# UKU207xx_power_board.net
KiCad netlist of a schematic drawn in Altium Designer
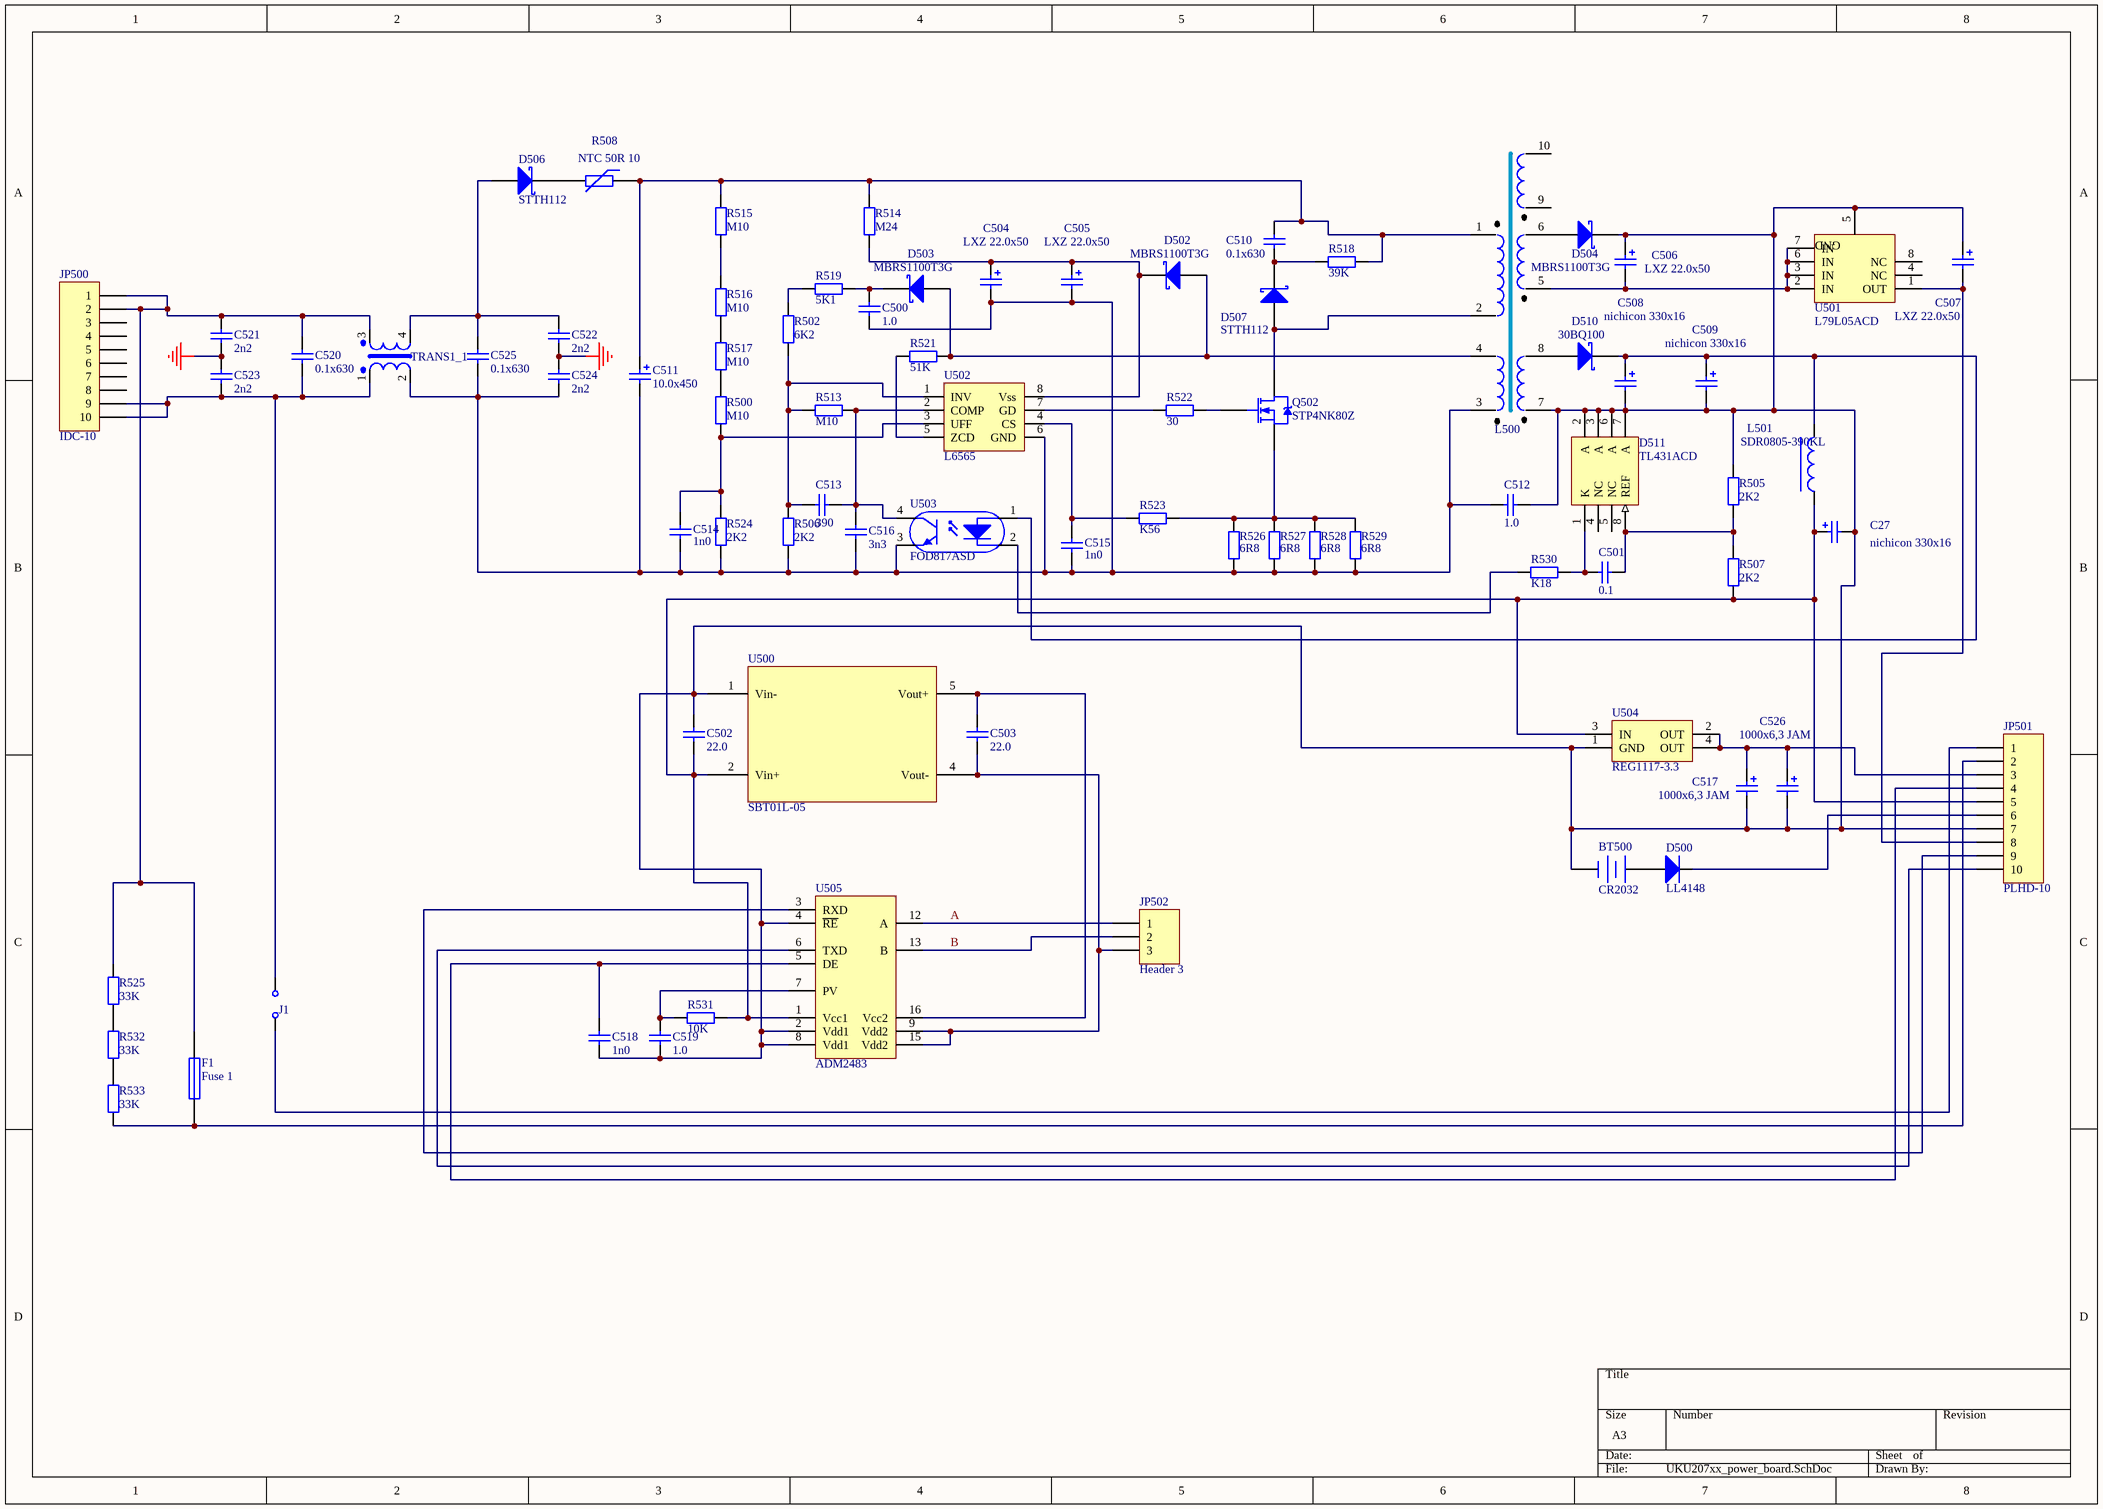
[diagram p0: UKU207xx_power_board.SchDoc]

(export (version "E")
  (design (tool "Eeschema 10.0.6"))
  (components
    (comp (ref "BT500")
      (value "CR2032")
      (footprint "BAT_SUPP")
      (description "Multicell Battery")
      (fields (field (name "MANUFACTURER") "Generic Components") (field (name "PUBLISHER") "Altium Limited"))
      (libsource (lib "Miscellaneous Devices") (part "Battery"))
    )
    (comp (ref "C27")
      (value "nichicon 330x16")
      (footprint "el3")
      (description "Polarized Capacitor (Radial)")
      (fields (field (name "MANUFACTURER") "Generic Components") (field (name "PUBLISHER") "Altium Limited"))
      (libsource (lib "PAL") (part "Cap Pol1"))
    )
    (comp (ref "C500")
      (value "1.0")
      (footprint "_1206")
      (description "Capacitor (Semiconductor SIM Model)")
      (fields (field (name "MANUFACTURER") "Generic Components") (field (name "PUBLISHER") "Altium Limited"))
      (libsource (lib "Miscellaneous Devices") (part "Cap Semi"))
    )
    (comp (ref "C501")
      (value "0.1")
      (footprint "_1206")
      (description "Capacitor (Semiconductor SIM Model)")
      (fields (field (name "MANUFACTURER") "Generic Components") (field (name "PUBLISHER") "Altium Limited"))
      (libsource (lib "Miscellaneous Devices") (part "Cap Semi"))
    )
    (comp (ref "C502")
      (value "22.0")
      (footprint "_1206")
      (description "Capacitor (Semiconductor SIM Model)")
      (fields (field (name "MANUFACTURER") "Generic Components") (field (name "PUBLISHER") "Altium Limited"))
      (libsource (lib "Miscellaneous Devices") (part "Cap Semi"))
    )
    (comp (ref "C503")
      (value "22.0")
      (footprint "_1206")
      (description "Capacitor (Semiconductor SIM Model)")
      (fields (field (name "MANUFACTURER") "Generic Components") (field (name "PUBLISHER") "Altium Limited"))
      (libsource (lib "Miscellaneous Devices") (part "Cap Semi"))
    )
    (comp (ref "C504")
      (value "LXZ 22.0x50")
      (footprint "el3")
      (description "Polarized Capacitor (Radial)")
      (fields (field (name "MANUFACTURER") "Generic Components") (field (name "PUBLISHER") "Altium Limited"))
      (libsource (lib "PAL") (part "Cap Pol1"))
    )
    (comp (ref "C505")
      (value "LXZ 22.0x50")
      (footprint "el3")
      (description "Polarized Capacitor (Radial)")
      (fields (field (name "MANUFACTURER") "Generic Components") (field (name "PUBLISHER") "Altium Limited"))
      (libsource (lib "PAL") (part "Cap Pol1"))
    )
    (comp (ref "C506")
      (value "LXZ 22.0x50")
      (footprint "el3")
      (description "Polarized Capacitor (Radial)")
      (fields (field (name "MANUFACTURER") "Generic Components") (field (name "PUBLISHER") "Altium Limited"))
      (libsource (lib "PAL") (part "Cap Pol1"))
    )
    (comp (ref "C507")
      (value "LXZ 22.0x50")
      (footprint "el3")
      (description "Polarized Capacitor (Radial)")
      (fields (field (name "MANUFACTURER") "Generic Components") (field (name "PUBLISHER") "Altium Limited"))
      (libsource (lib "PAL") (part "Cap Pol1"))
    )
    (comp (ref "C508")
      (value "nichicon 330x16")
      (footprint "el3")
      (description "Polarized Capacitor (Radial)")
      (fields (field (name "MANUFACTURER") "Generic Components") (field (name "PUBLISHER") "Altium Limited"))
      (libsource (lib "PAL") (part "Cap Pol1"))
    )
    (comp (ref "C509")
      (value "nichicon 330x16")
      (footprint "el3")
      (description "Polarized Capacitor (Radial)")
      (fields (field (name "MANUFACTURER") "Generic Components") (field (name "PUBLISHER") "Altium Limited"))
      (libsource (lib "PAL") (part "Cap Pol1"))
    )
    (comp (ref "C510")
      (value "0.1x630")
      (footprint "c15")
      (description "Capacitor (Semiconductor SIM Model)")
      (fields (field (name "MANUFACTURER") "Generic Components") (field (name "PUBLISHER") "Altium Limited"))
      (libsource (lib "Miscellaneous Devices") (part "Cap Semi"))
    )
    (comp (ref "C511")
      (value "10.0x450")
      (footprint "el_15_25_h")
      (description "Polarized Capacitor (Radial)")
      (fields (field (name "MANUFACTURER") "Generic Components") (field (name "PUBLISHER") "Altium Limited"))
      (libsource (lib "PAL") (part "Cap Pol1"))
    )
    (comp (ref "C512")
      (value "1.0")
      (footprint "C8")
      (description "Capacitor (Semiconductor SIM Model)")
      (fields (field (name "MANUFACTURER") "Generic Components") (field (name "PUBLISHER") "Altium Limited"))
      (libsource (lib "Miscellaneous Devices") (part "Cap Semi"))
    )
    (comp (ref "C513")
      (value "390")
      (footprint "_1206")
      (description "Capacitor (Semiconductor SIM Model)")
      (fields (field (name "MANUFACTURER") "Generic Components") (field (name "PUBLISHER") "Altium Limited"))
      (libsource (lib "Miscellaneous Devices") (part "Cap Semi"))
    )
    (comp (ref "C514")
      (value "1n0")
      (footprint "_1206")
      (description "Capacitor (Semiconductor SIM Model)")
      (fields (field (name "MANUFACTURER") "Generic Components") (field (name "PUBLISHER") "Altium Limited"))
      (libsource (lib "Miscellaneous Devices") (part "Cap Semi"))
    )
    (comp (ref "C515")
      (value "1n0")
      (footprint "_1206")
      (description "Capacitor (Semiconductor SIM Model)")
      (fields (field (name "MANUFACTURER") "Generic Components") (field (name "PUBLISHER") "Altium Limited"))
      (libsource (lib "Miscellaneous Devices") (part "Cap Semi"))
    )
    (comp (ref "C516")
      (value "3n3")
      (footprint "_1206")
      (description "Capacitor (Semiconductor SIM Model)")
      (fields (field (name "MANUFACTURER") "Generic Components") (field (name "PUBLISHER") "Altium Limited"))
      (libsource (lib "Miscellaneous Devices") (part "Cap Semi"))
    )
    (comp (ref "C517")
      (value "1000x6,3 JAM")
      (footprint "el3")
      (description "Polarized Capacitor (Radial)")
      (fields (field (name "MANUFACTURER") "Generic Components") (field (name "PUBLISHER") "Altium Limited"))
      (libsource (lib "PAL") (part "Cap Pol1"))
    )
    (comp (ref "C518")
      (value "1n0")
      (footprint "_1206")
      (description "Capacitor (Semiconductor SIM Model)")
      (fields (field (name "MANUFACTURER") "Generic Components") (field (name "PUBLISHER") "Altium Limited"))
      (libsource (lib "Miscellaneous Devices") (part "Cap Semi"))
    )
    (comp (ref "C519")
      (value "1.0")
      (footprint "_1206")
      (description "Capacitor (Semiconductor SIM Model)")
      (fields (field (name "MANUFACTURER") "Generic Components") (field (name "PUBLISHER") "Altium Limited"))
      (libsource (lib "Miscellaneous Devices") (part "Cap Semi"))
    )
    (comp (ref "C520")
      (value "0.1x630")
      (footprint "c15")
      (description "Capacitor (Semiconductor SIM Model)")
      (fields (field (name "MANUFACTURER") "Generic Components") (field (name "PUBLISHER") "Altium Limited"))
      (libsource (lib "Miscellaneous Devices") (part "Cap Semi"))
    )
    (comp (ref "C521")
      (value "2n2")
      (footprint "C8")
      (description "Capacitor (Semiconductor SIM Model)")
      (fields (field (name "MANUFACTURER") "Generic Components") (field (name "PUBLISHER") "Altium Limited"))
      (libsource (lib "Miscellaneous Devices") (part "Cap Semi"))
    )
    (comp (ref "C522")
      (value "2n2")
      (footprint "c8")
      (description "Capacitor (Semiconductor SIM Model)")
      (fields (field (name "MANUFACTURER") "Generic Components") (field (name "PUBLISHER") "Altium Limited"))
      (libsource (lib "Miscellaneous Devices") (part "Cap Semi"))
    )
    (comp (ref "C523")
      (value "2n2")
      (footprint "c8")
      (description "Capacitor (Semiconductor SIM Model)")
      (fields (field (name "MANUFACTURER") "Generic Components") (field (name "PUBLISHER") "Altium Limited"))
      (libsource (lib "Miscellaneous Devices") (part "Cap Semi"))
    )
    (comp (ref "C524")
      (value "2n2")
      (footprint "c8")
      (description "Capacitor (Semiconductor SIM Model)")
      (fields (field (name "MANUFACTURER") "Generic Components") (field (name "PUBLISHER") "Altium Limited"))
      (libsource (lib "Miscellaneous Devices") (part "Cap Semi"))
    )
    (comp (ref "C525")
      (value "0.1х630")
      (footprint "c15")
      (description "Capacitor (Semiconductor SIM Model)")
      (fields (field (name "MANUFACTURER") "Generic Components") (field (name "PUBLISHER") "Altium Limited"))
      (libsource (lib "Miscellaneous Devices") (part "Cap Semi"))
    )
    (comp (ref "C526")
      (value "1000x6,3 JAM")
      (footprint "el3")
      (description "Polarized Capacitor (Radial)")
      (fields (field (name "MANUFACTURER") "Generic Components") (field (name "PUBLISHER") "Altium Limited"))
      (libsource (lib "PAL") (part "Cap Pol1"))
    )
    (comp (ref "D500")
      (value "LL4148")
      (footprint "_1206d")
      (description "Default Diode")
      (fields (field (name "MANUFACTURER") "Generic Components") (field (name "PUBLISHER") "Altium Limited"))
      (libsource (lib "PAL") (part "Diode"))
    )
    (comp (ref "D502")
      (value "MBRS1100T3G")
      (footprint "D_6_3")
      (description "Schottky Rectifier")
      (fields
        (field (name "MANUFACTURER") "International Rectifier")
        (field (name "PUBLISHER") "Altium Limited")
      )
      (libsource (lib "IR Discrete Diode") (part "10BQ015"))
    )
    (comp (ref "D503")
      (value "MBRS1100T3G")
      (footprint "D_6_3")
      (description "Schottky Rectifier")
      (fields
        (field (name "MANUFACTURER") "International Rectifier")
        (field (name "PUBLISHER") "Altium Limited")
      )
      (libsource (lib "IR Discrete Diode") (part "10BQ015"))
    )
    (comp (ref "D504")
      (value "MBRS1100T3G")
      (footprint "D_6_3")
      (description "Schottky Rectifier")
      (fields
        (field (name "MANUFACTURER") "International Rectifier")
        (field (name "PUBLISHER") "Altium Limited")
      )
      (libsource (lib "IR Discrete Diode") (part "10BQ015"))
    )
    (comp (ref "D506")
      (value "STTH112")
      (footprint "D_6_3")
      (description "Schottky Diode")
      (fields
        (field (name "MANUFACTURER") "International Rectifier")
        (field (name "PUBLISHER") "Altium Limited")
      )
      (libsource (lib "IR Discrete Diode") (part "10BQ015"))
    )
    (comp (ref "D507")
      (value "STTH112")
      (footprint "D_6_3")
      (description "Schottky Diode")
      (fields
        (field (name "MANUFACTURER") "International Rectifier")
        (field (name "PUBLISHER") "Altium Limited")
      )
      (libsource (lib "IR Discrete Diode") (part "10BQ015"))
    )
    (comp (ref "D510")
      (value "30BQ100")
      (footprint "30BQ100")
      (description "Schottky Rectifier")
      (fields
        (field (name "MANUFACTURER") "International Rectifier")
        (field (name "PUBLISHER") "Altium Limited")
      )
      (libsource (lib "IR Discrete Diode") (part "10BQ015"))
    )
    (comp (ref "D511")
      (value "TL431ACD")
      (footprint "SO-G8")
      (description "Programmable Precision Reference")
      (fields (field (name "MANUFACTURER") "Motorola") (field (name "PUBLISHER") "Altium Limited"))
      (libsource (lib "Motorola Power Management Voltage Reference") (part "TL431ACD"))
    )
    (comp (ref "F1")
      (value "Fuse 1")
      (footprint "PIN-W2/E2.8")
      (description "Fuse")
      (fields (field (name "MANUFACTURER") "Generic Components") (field (name "PUBLISHER") "Altium Limited"))
      (libsource (lib "Miscellaneous Devices") (part "Fuse 1"))
    )
    (comp (ref "J1")
      (value "~")
      (footprint "BT5-2")
      (description "Switch")
      (fields (field (name "MANUFACTURER") "Generic Components") (field (name "PUBLISHER") "Altium Limited"))
      (libsource (lib "PAL") (part "JMP"))
    )
    (comp (ref "JP500")
      (value "IDC-10")
      (footprint "HDR2X5")
      (description "Header, 10-Pin")
      (fields (field (name "MANUFACTURER") "Generic Components") (field (name "PUBLISHER") "Altium Limited"))
      (libsource (lib "") (part "Header 10_1"))
    )
    (comp (ref "JP501")
      (value "PLHD-10")
      (footprint "HDR2X5")
      (description "Header, 10-Pin")
      (fields (field (name "MANUFACTURER") "Generic Components") (field (name "PUBLISHER") "Altium Limited"))
      (libsource (lib "Miscellaneous Connectors") (part "Header 10"))
    )
    (comp (ref "JP502")
      (value "Header 3")
      (footprint "2EDG-5.08-3P")
      (description "Header, 3-Pin")
      (fields (field (name "MANUFACTURER") "Generic Components") (field (name "PUBLISHER") "Altium Limited"))
      (libsource (lib "Miscellaneous Connectors") (part "Header 3"))
    )
    (comp (ref "L500")
      (value "L220-K10")
      (footprint "trans_ring1")
      (description "Дроссель")
      (libsource (lib "PAL") (part "L1_dc_2"))
    )
    (comp (ref "L501")
      (value "SDR0805-390KL")
      (footprint "L10x10")
      (description "Magnetic-Core Inductor")
      (fields (field (name "MANUFACTURER") "Generic Components") (field (name "PUBLISHER") "Altium Limited"))
      (libsource (lib "PAL") (part "Inductor Konstr 2"))
    )
    (comp (ref "Q502")
      (value "STP4NK80Z")
      (footprint "TO220_h")
      (description "N-Channel Power MOSFET")
      (fields (field (name "MANUFACTURER") "Generic Components") (field (name "PUBLISHER") "Altium Limited"))
      (libsource (lib "Miscellaneous Devices") (part "NMOS-2"))
    )
    (comp (ref "R500")
      (value "M10")
      (footprint "_1206")
      (description "Resistor")
      (fields (field (name "MANUFACTURER") "Generic Components") (field (name "PUBLISHER") "Altium Limited"))
      (libsource (lib "Miscellaneous Devices") (part "Res2"))
    )
    (comp (ref "R502")
      (value "6K2")
      (footprint "_1206")
      (description "Resistor")
      (fields (field (name "MANUFACTURER") "Generic Components") (field (name "PUBLISHER") "Altium Limited"))
      (libsource (lib "Miscellaneous Devices") (part "Res2"))
    )
    (comp (ref "R505")
      (value "2K2")
      (footprint "_1206")
      (description "Resistor")
      (fields (field (name "MANUFACTURER") "Generic Components") (field (name "PUBLISHER") "Altium Limited"))
      (libsource (lib "Miscellaneous Devices") (part "Res2"))
    )
    (comp (ref "R506")
      (value "2K2")
      (footprint "_1206")
      (description "Resistor")
      (fields (field (name "MANUFACTURER") "Generic Components") (field (name "PUBLISHER") "Altium Limited"))
      (libsource (lib "Miscellaneous Devices") (part "Res2"))
    )
    (comp (ref "R507")
      (value "2K2")
      (footprint "_1206")
      (description "Resistor")
      (fields (field (name "MANUFACTURER") "Generic Components") (field (name "PUBLISHER") "Altium Limited"))
      (libsource (lib "Miscellaneous Devices") (part "Res2"))
    )
    (comp (ref "R508")
      (value "NTC 50R 10")
      (footprint "JVR07N")
      (description "Varistor (Voltage-Sensitive Resistor)")
      (fields (field (name "MANUFACTURER") "Generic Components") (field (name "PUBLISHER") "Altium Limited"))
      (libsource (lib "Miscellaneous Devices") (part "Res Varistor"))
    )
    (comp (ref "R513")
      (value "M10")
      (footprint "_1206")
      (description "Resistor")
      (fields (field (name "MANUFACTURER") "Generic Components") (field (name "PUBLISHER") "Altium Limited"))
      (libsource (lib "") (part "Res2_1"))
    )
    (comp (ref "R514")
      (value "M24")
      (footprint "AXIAL-0.7")
      (description "Resistor")
      (fields (field (name "MANUFACTURER") "Generic Components") (field (name "PUBLISHER") "Altium Limited"))
      (libsource (lib "Miscellaneous Devices") (part "Res2"))
    )
    (comp (ref "R515")
      (value "M10")
      (footprint "_1206")
      (description "Resistor")
      (fields (field (name "MANUFACTURER") "Generic Components") (field (name "PUBLISHER") "Altium Limited"))
      (libsource (lib "Miscellaneous Devices") (part "Res2"))
    )
    (comp (ref "R516")
      (value "M10")
      (footprint "_1206")
      (description "Resistor")
      (fields (field (name "MANUFACTURER") "Generic Components") (field (name "PUBLISHER") "Altium Limited"))
      (libsource (lib "Miscellaneous Devices") (part "Res2"))
    )
    (comp (ref "R517")
      (value "M10")
      (footprint "_1206")
      (description "Resistor")
      (fields (field (name "MANUFACTURER") "Generic Components") (field (name "PUBLISHER") "Altium Limited"))
      (libsource (lib "Miscellaneous Devices") (part "Res2"))
    )
    (comp (ref "R518")
      (value "39K")
      (footprint "AXIAL-0.7")
      (description "Resistor")
      (fields (field (name "MANUFACTURER") "Generic Components") (field (name "PUBLISHER") "Altium Limited"))
      (libsource (lib "") (part "Res2_1"))
    )
    (comp (ref "R519")
      (value "5K1")
      (footprint "_1206")
      (description "Resistor")
      (fields (field (name "MANUFACTURER") "Generic Components") (field (name "PUBLISHER") "Altium Limited"))
      (libsource (lib "") (part "Res2_1"))
    )
    (comp (ref "R521")
      (value "51K")
      (footprint "_1206")
      (description "Resistor")
      (fields (field (name "MANUFACTURER") "Generic Components") (field (name "PUBLISHER") "Altium Limited"))
      (libsource (lib "") (part "Res2_1"))
    )
    (comp (ref "R522")
      (value "30")
      (footprint "_1206")
      (description "Resistor")
      (fields (field (name "MANUFACTURER") "Generic Components") (field (name "PUBLISHER") "Altium Limited"))
      (libsource (lib "") (part "Res2_1"))
    )
    (comp (ref "R523")
      (value "K56")
      (footprint "_1206")
      (description "Resistor")
      (fields (field (name "MANUFACTURER") "Generic Components") (field (name "PUBLISHER") "Altium Limited"))
      (libsource (lib "") (part "Res2_1"))
    )
    (comp (ref "R524")
      (value "2K2")
      (footprint "_1206")
      (description "Resistor")
      (fields (field (name "MANUFACTURER") "Generic Components") (field (name "PUBLISHER") "Altium Limited"))
      (libsource (lib "Miscellaneous Devices") (part "Res2"))
    )
    (comp (ref "R525")
      (value "33K")
      (footprint "_1206")
      (description "Resistor")
      (fields (field (name "MANUFACTURER") "Generic Components") (field (name "PUBLISHER") "Altium Limited"))
      (libsource (lib "Miscellaneous Devices") (part "Res2"))
    )
    (comp (ref "R526")
      (value "6R8")
      (footprint "_1206")
      (description "Resistor")
      (fields (field (name "MANUFACTURER") "Generic Components") (field (name "PUBLISHER") "Altium Limited"))
      (libsource (lib "") (part "Res2_2"))
    )
    (comp (ref "R527")
      (value "6R8")
      (footprint "_1206")
      (description "Resistor")
      (fields (field (name "MANUFACTURER") "Generic Components") (field (name "PUBLISHER") "Altium Limited"))
      (libsource (lib "") (part "Res2_2"))
    )
    (comp (ref "R528")
      (value "6R8")
      (footprint "_1206")
      (description "Resistor")
      (fields (field (name "MANUFACTURER") "Generic Components") (field (name "PUBLISHER") "Altium Limited"))
      (libsource (lib "") (part "Res2_2"))
    )
    (comp (ref "R529")
      (value "6R8")
      (footprint "_1206")
      (description "Resistor")
      (fields (field (name "MANUFACTURER") "Generic Components") (field (name "PUBLISHER") "Altium Limited"))
      (libsource (lib "") (part "Res2_2"))
    )
    (comp (ref "R530")
      (value "K18")
      (footprint "_1206")
      (description "Resistor")
      (fields (field (name "MANUFACTURER") "Generic Components") (field (name "PUBLISHER") "Altium Limited"))
      (libsource (lib "") (part "Res2_1"))
    )
    (comp (ref "R531")
      (value "10K")
      (footprint "_1206")
      (description "Resistor")
      (fields (field (name "MANUFACTURER") "Generic Components") (field (name "PUBLISHER") "Altium Limited"))
      (libsource (lib "") (part "Res2_1"))
    )
    (comp (ref "R532")
      (value "33K")
      (footprint "_1206")
      (description "Resistor")
      (fields (field (name "MANUFACTURER") "Generic Components") (field (name "PUBLISHER") "Altium Limited"))
      (libsource (lib "Miscellaneous Devices") (part "Res2"))
    )
    (comp (ref "R533")
      (value "33K")
      (footprint "_1206")
      (description "Resistor")
      (fields (field (name "MANUFACTURER") "Generic Components") (field (name "PUBLISHER") "Altium Limited"))
      (libsource (lib "Miscellaneous Devices") (part "Res2"))
    )
    (comp (ref "T500")
      (value "TRANS1_1")
      (footprint "3030R4")
      (fields (field (name "MANUFACTURER") "Generic Components") (field (name "PUBLISHER") "Altium Limited"))
      (libsource (lib "PAL") (part "TRANS1_1"))
    )
    (comp (ref "U500") (value "SBT01L-05") (footprint "SBT01DET01") (libsource (lib "PAL") (part "SBT01L")))
    (comp (ref "U501")
      (value "L79L05ACD")
      (footprint "SO-G8")
      (description "Negative Voltage Regulator")
      (fields (field (name "MANUFACTURER") "ST-Microelectronics") (field (name "PUBLISHER") "Altium Limited"))
      (libsource (lib "ST Power Mgt Voltage Regulator") (part "L79L05ACD"))
    )
    (comp (ref "U502") (value "L6565") (footprint "so-g8") (libsource (lib "PAL") (part "L6565")))
    (comp (ref "U503") (value "FOD817ASD") (footprint "FOD817ASD") (libsource (lib "PAL") (part "F00817ASD")))
    (comp (ref "U504")
      (value "REG1117-3.3")
      (footprint "DSO-G3")
      (description "800mA and 1A Low Dropout Positive Regulator 2.85V, 3.3V, 5V, and Adjustable")
      (fields (field (name "MANUFACTURER") "Burr-Brown") (field (name "PUBLISHER") "Altium Limited"))
      (libsource (lib "BB Power Mgt Voltage Regulator") (part "REG1117-3.3"))
    )
    (comp (ref "U505") (value "ADM2483") (footprint "SO-G16/D10.4") (libsource (lib "PAL") (part "ADM2483")))
  )
  (nets
    (net (code "1") (name "/A") (class "Default")
      (node (ref "JP502") (pin "1") (pinfunction "1_1") (pintype "passive"))
      (node (ref "U505") (pin "12") (pinfunction "A_12") (pintype "passive"))
    )
    (net (code "2") (name "/B") (class "Default")
      (node (ref "JP502") (pin "2") (pinfunction "2_2") (pintype "passive"))
      (node (ref "U505") (pin "13") (pinfunction "B_13") (pintype "passive"))
    )
    (net (code "3") (name "GND_GND") (class "Default")
      (node (ref "C521") (pin "1") (pinfunction "1_1") (pintype "passive"))
      (node (ref "C522") (pin "1") (pinfunction "1_1") (pintype "passive"))
      (node (ref "C523") (pin "2") (pinfunction "2_2") (pintype "passive"))
      (node (ref "C524") (pin "2") (pinfunction "2_2") (pintype "passive"))
    )
    (net (code "4") (name "Net-(BT500-+)") (class "Default")
      (node (ref "BT500") (pin "1") (pinfunction "+_1") (pintype "passive"))
      (node (ref "D500") (pin "1") (pinfunction "A_1") (pintype "passive"))
    )
    (net (code "5") (name "Net-(BT500--)") (class "Default")
      (node (ref "BT500") (pin "2") (pinfunction "-_2") (pintype "passive"))
      (node (ref "C27") (pin "2") (pinfunction "2_2") (pintype "passive"))
      (node (ref "C502") (pin "1") (pinfunction "1_1") (pintype "passive"))
      (node (ref "C506") (pin "1") (pinfunction "1_1") (pintype "passive"))
      (node (ref "C507") (pin "1") (pinfunction "1_1") (pintype "passive"))
      (node (ref "C508") (pin "2") (pinfunction "2_2") (pintype "passive"))
      (node (ref "C509") (pin "2") (pinfunction "2_2") (pintype "passive"))
      (node (ref "C512") (pin "1") (pinfunction "1_1") (pintype "passive"))
      (node (ref "C517") (pin "2") (pinfunction "2_2") (pintype "passive"))
      (node (ref "C518") (pin "1") (pinfunction "1_1") (pintype "passive"))
      (node (ref "C519") (pin "1") (pinfunction "1_1") (pintype "passive"))
      (node (ref "C526") (pin "2") (pinfunction "2_2") (pintype "passive"))
      (node (ref "D504") (pin "2") (pinfunction "K_2") (pintype "passive"))
      (node (ref "D511") (pin "2") (pinfunction "A_2") (pintype "passive"))
      (node (ref "D511") (pin "3") (pinfunction "A_3") (pintype "passive"))
      (node (ref "D511") (pin "6") (pinfunction "A_6") (pintype "passive"))
      (node (ref "D511") (pin "7") (pinfunction "A_7") (pintype "passive"))
      (node (ref "JP501") (pin "7") (pinfunction "7_7") (pintype "passive"))
      (node (ref "L500") (pin "7") (pintype "passive"))
      (node (ref "R505") (pin "2") (pinfunction "2_2") (pintype "passive"))
      (node (ref "U500") (pin "1") (pinfunction "Vin-_1") (pintype "passive"))
      (node (ref "U501") (pin "5") (pinfunction "GND_5") (pintype "power_in"))
      (node (ref "U504") (pin "1") (pinfunction "GND_1") (pintype "power_in"))
      (node (ref "U505") (pin "2") (pinfunction "Vdd1_2") (pintype "passive"))
      (node (ref "U505") (pin "4") (pinfunction "~{RE}_4") (pintype "passive"))
      (node (ref "U505") (pin "8") (pinfunction "Vdd1_8") (pintype "passive"))
    )
    (net (code "6") (name "Net-(C506-Pad2)") (class "Default")
      (node (ref "C506") (pin "2") (pinfunction "2_2") (pintype "passive"))
      (node (ref "L500") (pin "5") (pintype "passive"))
      (node (ref "U501") (pin "2") (pinfunction "IN_2") (pintype "power_in"))
      (node (ref "U501") (pin "3") (pinfunction "IN_3") (pintype "power_in"))
      (node (ref "U501") (pin "6") (pinfunction "IN_6") (pintype "power_in"))
      (node (ref "U501") (pin "7") (pinfunction "IN_7") (pintype "power_in"))
    )
    (net (code "7") (name "Net-(C510-Pad2)") (class "Default")
      (node (ref "C510") (pin "2") (pinfunction "2_2") (pintype "passive"))
      (node (ref "C511") (pin "1") (pinfunction "1_1") (pintype "passive"))
      (node (ref "L500") (pin "1") (pintype "passive"))
      (node (ref "R508") (pin "1") (pinfunction "1_1") (pintype "passive"))
      (node (ref "R514") (pin "2") (pinfunction "2_2") (pintype "passive"))
      (node (ref "R515") (pin "2") (pinfunction "2_2") (pintype "passive"))
      (node (ref "R518") (pin "1") (pinfunction "1_1") (pintype "passive"))
    )
    (net (code "8") (name "Net-(C517-Pad1)") (class "Default")
      (node (ref "C517") (pin "1") (pinfunction "1_1") (pintype "passive"))
      (node (ref "C526") (pin "1") (pinfunction "1_1") (pintype "passive"))
      (node (ref "JP501") (pin "3") (pinfunction "3_3") (pintype "passive"))
      (node (ref "U504") (pin "2") (pinfunction "OUT_2") (pintype "power_in"))
      (node (ref "U504") (pin "4") (pinfunction "OUT_4") (pintype "power_in"))
    )
    (net (code "9") (name "Net-(D500-K)") (class "Default")
      (node (ref "D500") (pin "2") (pinfunction "K_2") (pintype "passive"))
      (node (ref "JP501") (pin "6") (pinfunction "6_6") (pintype "passive"))
    )
    (net (code "10") (name "Net-(D502-A)") (class "Default")
      (node (ref "D502") (pin "1") (pinfunction "A_1") (pintype "passive"))
      (node (ref "D503") (pin "1") (pinfunction "A_1") (pintype "passive"))
      (node (ref "L500") (pin "4") (pintype "passive"))
      (node (ref "R521") (pin "1") (pinfunction "1_1") (pintype "passive"))
    )
    (net (code "11") (name "Net-(D502-K)") (class "Default")
      (node (ref "C504") (pin "1") (pinfunction "1_1") (pintype "passive"))
      (node (ref "C505") (pin "1") (pinfunction "1_1") (pintype "passive"))
      (node (ref "D502") (pin "2") (pinfunction "K_2") (pintype "passive"))
      (node (ref "R514") (pin "1") (pinfunction "1_1") (pintype "passive"))
      (node (ref "U502") (pin "8") (pinfunction "Vss_8") (pintype "passive"))
    )
    (net (code "12") (name "Net-(D503-K)") (class "Default")
      (node (ref "C500") (pin "2") (pinfunction "2_2") (pintype "passive"))
      (node (ref "D503") (pin "2") (pinfunction "K_2") (pintype "passive"))
      (node (ref "R519") (pin "1") (pinfunction "1_1") (pintype "passive"))
    )
    (net (code "13") (name "Net-(D504-A)") (class "Default")
      (node (ref "D504") (pin "1") (pinfunction "A_1") (pintype "passive"))
      (node (ref "L500") (pin "6") (pintype "passive"))
    )
    (net (code "14") (name "Net-(D506-A)") (class "Default")
      (node (ref "C522") (pin "2") (pinfunction "2_2") (pintype "passive"))
      (node (ref "C525") (pin "2") (pinfunction "2_2") (pintype "passive"))
      (node (ref "D506") (pin "1") (pinfunction "A_1") (pintype "passive"))
      (node (ref "T500") (pin "4") (pinfunction "Sec1-_4") (pintype "passive"))
    )
    (net (code "15") (name "Net-(D506-K)") (class "Default")
      (node (ref "D506") (pin "2") (pinfunction "K_2") (pintype "passive"))
      (node (ref "R508") (pin "2") (pinfunction "2_2") (pintype "passive"))
    )
    (net (code "16") (name "Net-(D507-A)") (class "Default")
      (node (ref "D507") (pin "1") (pinfunction "A_1") (pintype "passive"))
      (node (ref "L500") (pin "2") (pintype "passive"))
      (node (ref "Q502") (pin "2") (pinfunction "D_2") (pintype "passive"))
    )
    (net (code "17") (name "Net-(D507-K)") (class "Default")
      (node (ref "C510") (pin "1") (pinfunction "1_1") (pintype "passive"))
      (node (ref "D507") (pin "2") (pinfunction "K_2") (pintype "passive"))
      (node (ref "R518") (pin "2") (pinfunction "2_2") (pintype "passive"))
    )
    (net (code "18") (name "Net-(D510-A)") (class "Default")
      (node (ref "D510") (pin "1") (pinfunction "A_1") (pintype "passive"))
      (node (ref "L500") (pin "8") (pintype "passive"))
    )
    (net (code "19") (name "Net-(D510-K)") (class "Default")
      (node (ref "C508") (pin "1") (pinfunction "1_1") (pintype "passive"))
      (node (ref "C509") (pin "1") (pinfunction "1_1") (pintype "passive"))
      (node (ref "D510") (pin "2") (pinfunction "K_2") (pintype "passive"))
      (node (ref "L501") (pin "2") (pinfunction "2_2") (pintype "passive"))
      (node (ref "U503") (pin "1") (pinfunction "0_1") (pintype "passive"))
    )
    (net (code "20") (name "Net-(D511-K)") (class "Default")
      (node (ref "C501") (pin "2") (pinfunction "2_2") (pintype "passive"))
      (node (ref "D511") (pin "1") (pinfunction "K_1") (pintype "passive"))
      (node (ref "R530") (pin "1") (pinfunction "1_1") (pintype "passive"))
    )
    (net (code "21") (name "Net-(D511-REF)") (class "Default")
      (node (ref "C501") (pin "1") (pinfunction "1_1") (pintype "passive"))
      (node (ref "D511") (pin "8") (pinfunction "REF_8") (pintype "input"))
      (node (ref "R505") (pin "1") (pinfunction "1_1") (pintype "passive"))
      (node (ref "R507") (pin "2") (pinfunction "2_2") (pintype "passive"))
    )
    (net (code "22") (name "Net-(F1-Pad1)") (class "Default")
      (node (ref "F1") (pin "1") (pinfunction "1_1") (pintype "passive"))
      (node (ref "JP501") (pin "2") (pinfunction "2_2") (pintype "passive"))
      (node (ref "R533") (pin "1") (pinfunction "1_1") (pintype "passive"))
    )
    (net (code "23") (name "Net-(J1-Pad2)") (class "Default")
      (node (ref "J1") (pin "2") (pinfunction "2_2") (pintype "passive"))
      (node (ref "JP501") (pin "1") (pinfunction "1_1") (pintype "passive"))
    )
    (net (code "24") (name "Net-(Q502-G)") (class "Default")
      (node (ref "Q502") (pin "1") (pinfunction "G_1") (pintype "passive"))
      (node (ref "R522") (pin "1") (pinfunction "1_1") (pintype "passive"))
    )
    (net (code "25") (name "Net-(Q502-S)") (class "Default")
      (node (ref "Q502") (pin "3") (pinfunction "S_3") (pintype "passive"))
      (node (ref "R523") (pin "1") (pinfunction "1_1") (pintype "passive"))
      (node (ref "R526") (pin "1") (pinfunction "1_1") (pintype "passive"))
      (node (ref "R527") (pin "1") (pinfunction "1_1") (pintype "passive"))
      (node (ref "R528") (pin "1") (pinfunction "1_1") (pintype "passive"))
      (node (ref "R529") (pin "1") (pinfunction "1_1") (pintype "passive"))
    )
    (net (code "26") (name "Net-(R500-Pad2)") (class "Default")
      (node (ref "R500") (pin "2") (pinfunction "2_2") (pintype "passive"))
      (node (ref "R517") (pin "1") (pinfunction "1_1") (pintype "passive"))
    )
    (net (code "27") (name "Net-(R502-Pad2)") (class "Default")
      (node (ref "R502") (pin "2") (pinfunction "2_2") (pintype "passive"))
      (node (ref "R519") (pin "2") (pinfunction "2_2") (pintype "passive"))
    )
    (net (code "28") (name "Net-(R515-Pad1)") (class "Default")
      (node (ref "R515") (pin "1") (pinfunction "1_1") (pintype "passive"))
      (node (ref "R516") (pin "2") (pinfunction "2_2") (pintype "passive"))
    )
    (net (code "29") (name "Net-(R516-Pad1)") (class "Default")
      (node (ref "R516") (pin "1") (pinfunction "1_1") (pintype "passive"))
      (node (ref "R517") (pin "2") (pinfunction "2_2") (pintype "passive"))
    )
    (net (code "30") (name "Net-(R525-Pad1)") (class "Default")
      (node (ref "R525") (pin "1") (pinfunction "1_1") (pintype "passive"))
      (node (ref "R532") (pin "2") (pinfunction "2_2") (pintype "passive"))
    )
    (net (code "31") (name "Net-(R532-Pad1)") (class "Default")
      (node (ref "R532") (pin "1") (pinfunction "1_1") (pintype "passive"))
      (node (ref "R533") (pin "2") (pinfunction "2_2") (pintype "passive"))
    )
    (net (code "32") (name "Net-(T500-Pri+)") (class "Default")
      (node (ref "C520") (pin "1") (pinfunction "1_1") (pintype "passive"))
      (node (ref "C523") (pin "1") (pinfunction "1_1") (pintype "passive"))
      (node (ref "J1") (pin "1") (pinfunction "1_1") (pintype "passive"))
      (node (ref "JP500") (pin "10") (pinfunction "10_10") (pintype "passive"))
      (node (ref "JP500") (pin "9") (pinfunction "9_9") (pintype "passive"))
      (node (ref "T500") (pin "1") (pinfunction "Pri+_1") (pintype "passive"))
    )
    (net (code "33") (name "Net-(T500-Pri-)") (class "Default")
      (node (ref "C500") (pin "1") (pinfunction "1_1") (pintype "passive"))
      (node (ref "C504") (pin "2") (pinfunction "2_2") (pintype "passive"))
      (node (ref "C505") (pin "2") (pinfunction "2_2") (pintype "passive"))
      (node (ref "C511") (pin "2") (pinfunction "2_2") (pintype "passive"))
      (node (ref "C512") (pin "2") (pinfunction "2_2") (pintype "passive"))
      (node (ref "C514") (pin "2") (pinfunction "2_2") (pintype "passive"))
      (node (ref "C515") (pin "2") (pinfunction "2_2") (pintype "passive"))
      (node (ref "C516") (pin "1") (pinfunction "1_1") (pintype "passive"))
      (node (ref "C524") (pin "1") (pinfunction "1_1") (pintype "passive"))
      (node (ref "C525") (pin "1") (pinfunction "1_1") (pintype "passive"))
      (node (ref "L500") (pin "3") (pintype "passive"))
      (node (ref "R506") (pin "1") (pinfunction "1_1") (pintype "passive"))
      (node (ref "R524") (pin "1") (pinfunction "1_1") (pintype "passive"))
      (node (ref "R526") (pin "2") (pinfunction "2_2") (pintype "passive"))
      (node (ref "R527") (pin "2") (pinfunction "2_2") (pintype "passive"))
      (node (ref "R528") (pin "2") (pinfunction "2_2") (pintype "passive"))
      (node (ref "R529") (pin "2") (pinfunction "2_2") (pintype "passive"))
      (node (ref "T500") (pin "2") (pinfunction "Pri-_2") (pintype "passive"))
      (node (ref "U502") (pin "6") (pinfunction "GND_6") (pintype "passive"))
      (node (ref "U503") (pin "3") (pinfunction "4_3") (pintype "passive"))
    )
    (net (code "34") (name "Net-(T500-Sec1+)") (class "Default")
      (node (ref "C520") (pin "2") (pinfunction "2_2") (pintype "passive"))
      (node (ref "C521") (pin "2") (pinfunction "2_2") (pintype "passive"))
      (node (ref "F1") (pin "2") (pinfunction "2_2") (pintype "passive"))
      (node (ref "JP500") (pin "1") (pinfunction "1_1") (pintype "passive"))
      (node (ref "JP500") (pin "2") (pinfunction "2_2") (pintype "passive"))
      (node (ref "R525") (pin "2") (pinfunction "2_2") (pintype "passive"))
      (node (ref "T500") (pin "3") (pinfunction "Sec1+_3") (pintype "passive"))
    )
    (net (code "35") (name "Net-(U500-Vin+)") (class "Default")
      (node (ref "C27") (pin "1") (pinfunction "1_1") (pintype "passive"))
      (node (ref "C502") (pin "2") (pinfunction "2_2") (pintype "passive"))
      (node (ref "JP501") (pin "5") (pinfunction "5_5") (pintype "passive"))
      (node (ref "L501") (pin "1") (pinfunction "1_1") (pintype "passive"))
      (node (ref "R507") (pin "1") (pinfunction "1_1") (pintype "passive"))
      (node (ref "R531") (pin "1") (pinfunction "1_1") (pintype "passive"))
      (node (ref "U500") (pin "2") (pinfunction "Vin+_2") (pintype "passive"))
      (node (ref "U504") (pin "3") (pinfunction "IN_3") (pintype "power_in"))
      (node (ref "U505") (pin "1") (pinfunction "Vcc1_1") (pintype "passive"))
    )
    (net (code "36") (name "Net-(U500-Vout+)") (class "Default")
      (node (ref "C503") (pin "1") (pinfunction "1_1") (pintype "passive"))
      (node (ref "U500") (pin "5") (pinfunction "Vout+_5") (pintype "passive"))
      (node (ref "U505") (pin "16") (pinfunction "Vcc2_16") (pintype "passive"))
    )
    (net (code "37") (name "Net-(U500-Vout-)") (class "Default")
      (node (ref "C503") (pin "2") (pinfunction "2_2") (pintype "passive"))
      (node (ref "JP502") (pin "3") (pinfunction "3_3") (pintype "passive"))
      (node (ref "U500") (pin "4") (pinfunction "Vout-_4") (pintype "passive"))
      (node (ref "U505") (pin "15") (pinfunction "Vdd2_15") (pintype "passive"))
      (node (ref "U505") (pin "9") (pinfunction "Vdd2_9") (pintype "passive"))
    )
    (net (code "38") (name "Net-(U501-OUT)") (class "Default")
      (node (ref "C507") (pin "2") (pinfunction "2_2") (pintype "passive"))
      (node (ref "JP501") (pin "8") (pinfunction "8_8") (pintype "passive"))
      (node (ref "U501") (pin "1") (pinfunction "OUT_1") (pintype "power_in"))
    )
    (net (code "39") (name "Net-(U502-COMP)") (class "Default")
      (node (ref "C513") (pin "2") (pinfunction "2_2") (pintype "passive"))
      (node (ref "C516") (pin "2") (pinfunction "2_2") (pintype "passive"))
      (node (ref "R513") (pin "1") (pinfunction "1_1") (pintype "passive"))
      (node (ref "U502") (pin "2") (pinfunction "COMP_2") (pintype "passive"))
      (node (ref "U503") (pin "4") (pinfunction "2_4") (pintype "passive"))
    )
    (net (code "40") (name "Net-(U502-CS)") (class "Default")
      (node (ref "C515") (pin "1") (pinfunction "1_1") (pintype "passive"))
      (node (ref "R523") (pin "2") (pinfunction "2_2") (pintype "passive"))
      (node (ref "U502") (pin "4") (pinfunction "CS_4") (pintype "passive"))
    )
    (net (code "41") (name "Net-(U502-GD)") (class "Default")
      (node (ref "R522") (pin "2") (pinfunction "2_2") (pintype "passive"))
      (node (ref "U502") (pin "7") (pinfunction "GD_7") (pintype "passive"))
    )
    (net (code "42") (name "Net-(U502-INV)") (class "Default")
      (node (ref "C513") (pin "1") (pinfunction "1_1") (pintype "passive"))
      (node (ref "R502") (pin "1") (pinfunction "1_1") (pintype "passive"))
      (node (ref "R506") (pin "2") (pinfunction "2_2") (pintype "passive"))
      (node (ref "R513") (pin "2") (pinfunction "2_2") (pintype "passive"))
      (node (ref "U502") (pin "1") (pinfunction "INV_1") (pintype "passive"))
    )
    (net (code "43") (name "Net-(U502-UFF)") (class "Default")
      (node (ref "C514") (pin "1") (pinfunction "1_1") (pintype "passive"))
      (node (ref "R500") (pin "1") (pinfunction "1_1") (pintype "passive"))
      (node (ref "R524") (pin "2") (pinfunction "2_2") (pintype "passive"))
      (node (ref "U502") (pin "3") (pinfunction "UFF_3") (pintype "passive"))
    )
    (net (code "44") (name "Net-(U502-ZCD)") (class "Default")
      (node (ref "R521") (pin "2") (pinfunction "2_2") (pintype "passive"))
      (node (ref "U502") (pin "5") (pinfunction "ZCD_5") (pintype "passive"))
    )
    (net (code "45") (name "Net-(U503-1)") (class "Default")
      (node (ref "R530") (pin "2") (pinfunction "2_2") (pintype "passive"))
      (node (ref "U503") (pin "2") (pinfunction "1_2") (pintype "passive"))
    )
    (net (code "46") (name "Net-(U505-DE)") (class "Default")
      (node (ref "C518") (pin "2") (pinfunction "2_2") (pintype "passive"))
      (node (ref "JP501") (pin "4") (pinfunction "4_4") (pintype "passive"))
      (node (ref "U505") (pin "5") (pinfunction "DE_5") (pintype "passive"))
    )
    (net (code "47") (name "Net-(U505-PV)") (class "Default")
      (node (ref "C519") (pin "2") (pinfunction "2_2") (pintype "passive"))
      (node (ref "R531") (pin "2") (pinfunction "2_2") (pintype "passive"))
      (node (ref "U505") (pin "7") (pinfunction "PV_7") (pintype "passive"))
    )
    (net (code "48") (name "Net-(U505-RXD)") (class "Default")
      (node (ref "JP501") (pin "9") (pinfunction "9_9") (pintype "passive"))
      (node (ref "U505") (pin "3") (pinfunction "RXD_3") (pintype "passive"))
    )
    (net (code "49") (name "Net-(U505-TXD)") (class "Default")
      (node (ref "JP501") (pin "10") (pinfunction "10_10") (pintype "passive"))
      (node (ref "U505") (pin "6") (pinfunction "TXD_6") (pintype "passive"))
    )
    (net (code "50") (name "unconnected-(D511-NC-Pad4)") (class "Default")
      (node (ref "D511") (pin "4") (pinfunction "NC_4") (pintype "passive"))
    )
    (net (code "51") (name "unconnected-(D511-NC-Pad5)") (class "Default")
      (node (ref "D511") (pin "5") (pinfunction "NC_5") (pintype "passive"))
    )
    (net (code "52") (name "unconnected-(JP500-Pad3)") (class "Default")
      (node (ref "JP500") (pin "3") (pinfunction "3_3") (pintype "passive"))
    )
    (net (code "53") (name "unconnected-(JP500-Pad4)") (class "Default")
      (node (ref "JP500") (pin "4") (pinfunction "4_4") (pintype "passive"))
    )
    (net (code "54") (name "unconnected-(JP500-Pad5)") (class "Default")
      (node (ref "JP500") (pin "5") (pinfunction "5_5") (pintype "passive"))
    )
    (net (code "55") (name "unconnected-(JP500-Pad6)") (class "Default")
      (node (ref "JP500") (pin "6") (pinfunction "6_6") (pintype "passive"))
    )
    (net (code "56") (name "unconnected-(JP500-Pad7)") (class "Default")
      (node (ref "JP500") (pin "7") (pinfunction "7_7") (pintype "passive"))
    )
    (net (code "57") (name "unconnected-(JP500-Pad8)") (class "Default")
      (node (ref "JP500") (pin "8") (pinfunction "8_8") (pintype "passive"))
    )
    (net (code "58") (name "unconnected-(L500-Pad9)") (class "Default")
      (node (ref "L500") (pin "9") (pintype "passive"))
    )
    (net (code "59") (name "unconnected-(L500-Pad10)") (class "Default")
      (node (ref "L500") (pin "10") (pinfunction "10_10") (pintype "passive"))
    )
    (net (code "60") (name "unconnected-(U501-NC-Pad4)") (class "Default")
      (node (ref "U501") (pin "4") (pinfunction "NC_4") (pintype "passive"))
    )
    (net (code "61") (name "unconnected-(U501-NC-Pad8)") (class "Default")
      (node (ref "U501") (pin "8") (pinfunction "NC_8") (pintype "passive"))
    )
  )
)
